# opam.net
KiCad netlist of a schematic drawn in EAGLE
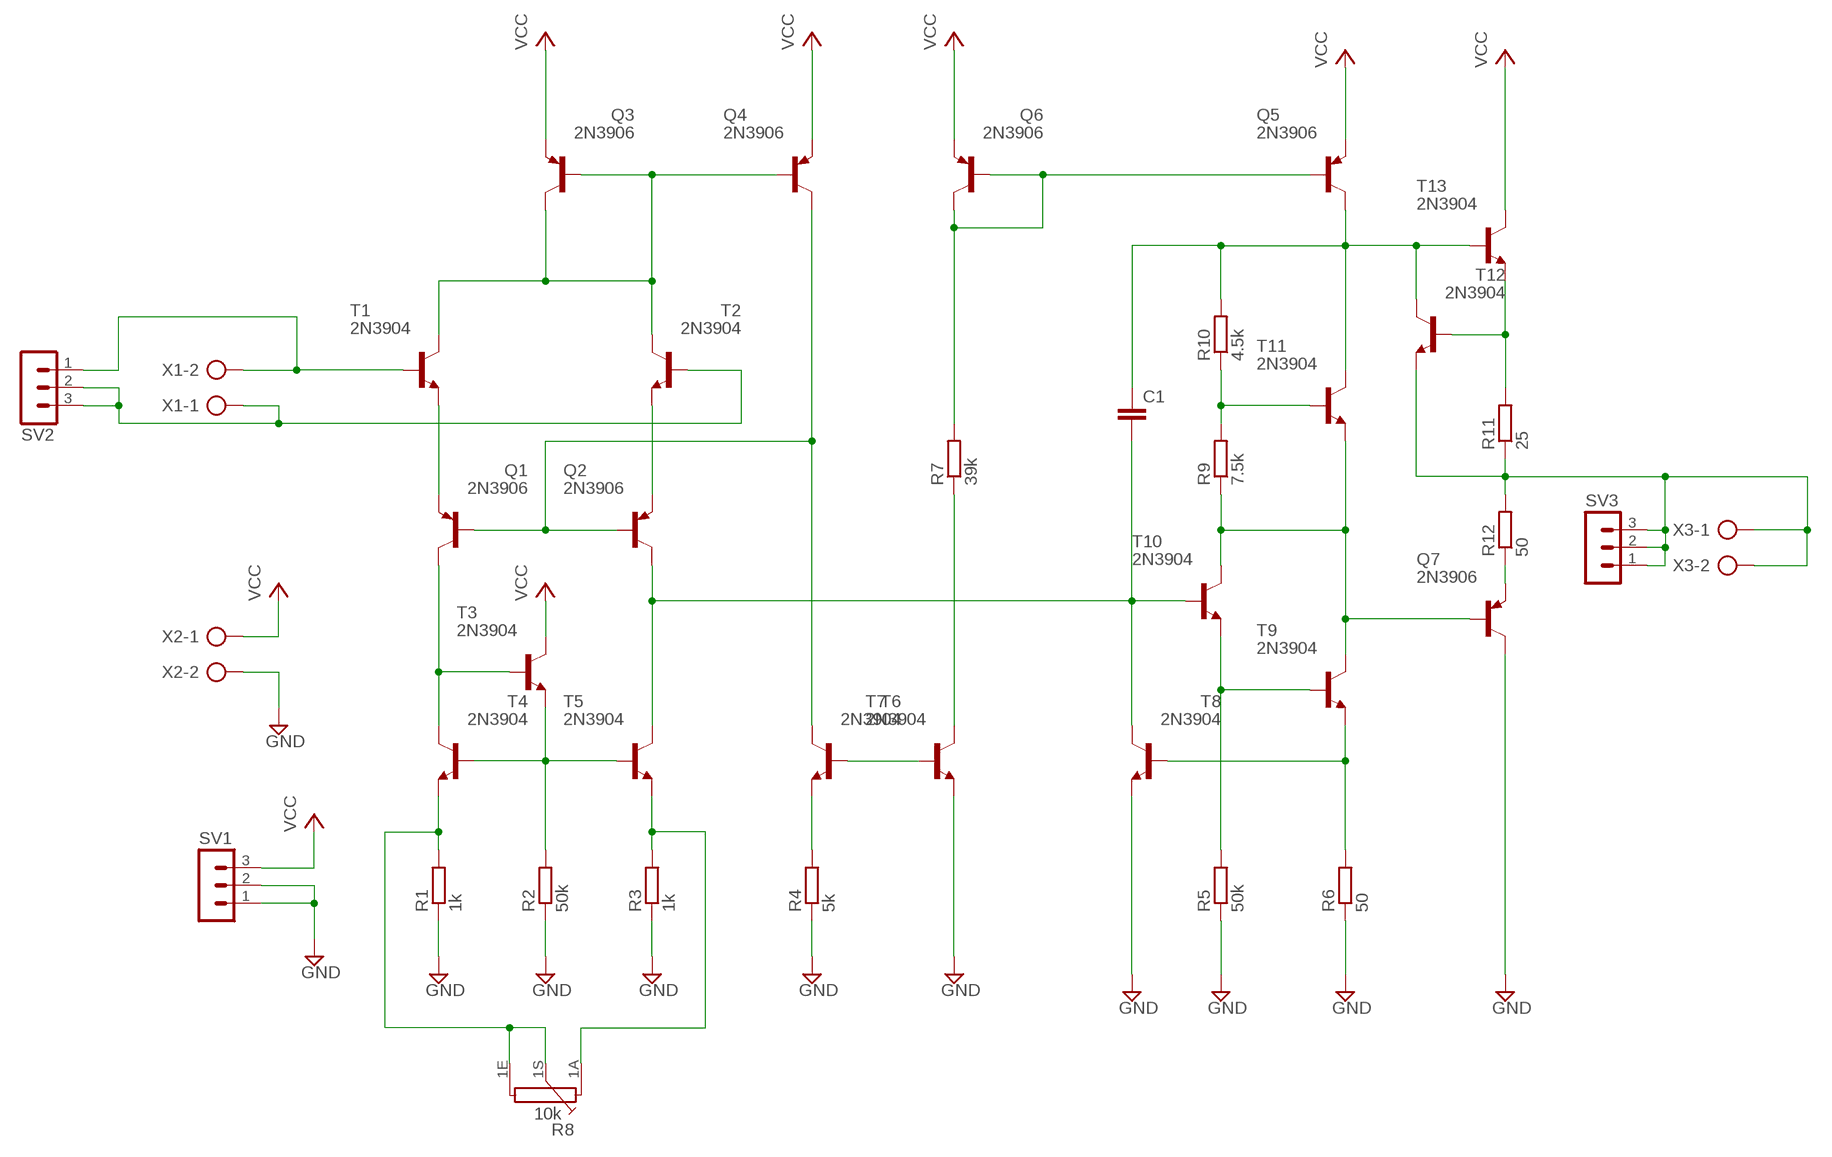
[diagram p0: schematic, sheet 1]

(export (version "E")
  (design (tool "Eeschema 10.0.6"))
  (components
    (comp (ref "C1")
      (value "C2.5/5")
      (footprint "eagle-import:C2.5-5")
      (libsource (lib "eagle-import") (part "C2.5/5"))
    )
    (comp (ref "Q1")
      (value "2N3906")
      (footprint "eagle-import:TO92")
      (libsource (lib "eagle-import") (part "2N3906"))
    )
    (comp (ref "Q2")
      (value "2N3906")
      (footprint "eagle-import:TO92")
      (libsource (lib "eagle-import") (part "2N3906"))
    )
    (comp (ref "Q3")
      (value "2N3906")
      (footprint "eagle-import:TO92")
      (libsource (lib "eagle-import") (part "2N3906"))
    )
    (comp (ref "Q4")
      (value "2N3906")
      (footprint "eagle-import:TO92")
      (libsource (lib "eagle-import") (part "2N3906"))
    )
    (comp (ref "Q5")
      (value "2N3906")
      (footprint "eagle-import:TO92")
      (libsource (lib "eagle-import") (part "2N3906"))
    )
    (comp (ref "Q6")
      (value "2N3906")
      (footprint "eagle-import:TO92")
      (libsource (lib "eagle-import") (part "2N3906"))
    )
    (comp (ref "Q7")
      (value "2N3906")
      (footprint "eagle-import:TO92")
      (libsource (lib "eagle-import") (part "2N3906"))
    )
    (comp (ref "R1")
      (value "1k")
      (footprint "eagle-import:0309_12")
      (libsource (lib "eagle-import") (part "R-EU_0309/12"))
    )
    (comp (ref "R2")
      (value "50k")
      (footprint "eagle-import:0309_12")
      (libsource (lib "eagle-import") (part "R-EU_0309/12"))
    )
    (comp (ref "R3")
      (value "1k")
      (footprint "eagle-import:0309_12")
      (libsource (lib "eagle-import") (part "R-EU_0309/12"))
    )
    (comp (ref "R4")
      (value "5k")
      (footprint "eagle-import:0309_12")
      (libsource (lib "eagle-import") (part "R-EU_0309/12"))
    )
    (comp (ref "R5")
      (value "50k")
      (footprint "eagle-import:0309_12")
      (libsource (lib "eagle-import") (part "R-EU_0309/12"))
    )
    (comp (ref "R6")
      (value "50")
      (footprint "eagle-import:0309_12")
      (libsource (lib "eagle-import") (part "R-EU_0309/12"))
    )
    (comp (ref "R7")
      (value "39k")
      (footprint "eagle-import:0309_12")
      (libsource (lib "eagle-import") (part "R-EU_0309/12"))
    )
    (comp (ref "R8")
      (value "10k")
      (footprint "eagle-import:PC16S")
      (libsource (lib "eagle-import") (part "PC16S"))
    )
    (comp (ref "R9")
      (value "7.5k")
      (footprint "eagle-import:0309_12")
      (libsource (lib "eagle-import") (part "R-EU_0309/12"))
    )
    (comp (ref "R10")
      (value "4.5k")
      (footprint "eagle-import:0309_12")
      (libsource (lib "eagle-import") (part "R-EU_0309/12"))
    )
    (comp (ref "R11")
      (value "25")
      (footprint "eagle-import:0309_12")
      (libsource (lib "eagle-import") (part "R-EU_0309/12"))
    )
    (comp (ref "R12")
      (value "50")
      (footprint "eagle-import:0309_12")
      (libsource (lib "eagle-import") (part "R-EU_0309/12"))
    )
    (comp (ref "SV1")
      (value "MA03-1")
      (footprint "eagle-import:MA03-1")
      (libsource (lib "eagle-import") (part "MA03-1"))
    )
    (comp (ref "SV2")
      (value "MA03-1")
      (footprint "eagle-import:MA03-1")
      (libsource (lib "eagle-import") (part "MA03-1"))
    )
    (comp (ref "SV3")
      (value "MA03-1")
      (footprint "eagle-import:MA03-1")
      (libsource (lib "eagle-import") (part "MA03-1"))
    )
    (comp (ref "T1")
      (value "2N3904")
      (footprint "eagle-import:TO92")
      (libsource (lib "eagle-import") (part "2N3904"))
    )
    (comp (ref "T2")
      (value "2N3904")
      (footprint "eagle-import:TO92")
      (libsource (lib "eagle-import") (part "2N3904"))
    )
    (comp (ref "T3")
      (value "2N3904")
      (footprint "eagle-import:TO92")
      (libsource (lib "eagle-import") (part "2N3904"))
    )
    (comp (ref "T4")
      (value "2N3904")
      (footprint "eagle-import:TO92")
      (libsource (lib "eagle-import") (part "2N3904"))
    )
    (comp (ref "T5")
      (value "2N3904")
      (footprint "eagle-import:TO92")
      (libsource (lib "eagle-import") (part "2N3904"))
    )
    (comp (ref "T6")
      (value "2N3904")
      (footprint "eagle-import:TO92")
      (libsource (lib "eagle-import") (part "2N3904"))
    )
    (comp (ref "T7")
      (value "2N3904")
      (footprint "eagle-import:TO92")
      (libsource (lib "eagle-import") (part "2N3904"))
    )
    (comp (ref "T8")
      (value "2N3904")
      (footprint "eagle-import:TO92")
      (libsource (lib "eagle-import") (part "2N3904"))
    )
    (comp (ref "T9")
      (value "2N3904")
      (footprint "eagle-import:TO92")
      (libsource (lib "eagle-import") (part "2N3904"))
    )
    (comp (ref "T10")
      (value "2N3904")
      (footprint "eagle-import:TO92")
      (libsource (lib "eagle-import") (part "2N3904"))
    )
    (comp (ref "T11")
      (value "2N3904")
      (footprint "eagle-import:TO92")
      (libsource (lib "eagle-import") (part "2N3904"))
    )
    (comp (ref "T12")
      (value "2N3904")
      (footprint "eagle-import:TO92")
      (libsource (lib "eagle-import") (part "2N3904"))
    )
    (comp (ref "T13")
      (value "2N3904")
      (footprint "eagle-import:TO92")
      (libsource (lib "eagle-import") (part "2N3904"))
    )
    (comp (ref "X1")
      (value "AK500/2-H")
      (footprint "eagle-import:AK500_2-H")
      (libsource (lib "eagle-import") (part "AK500/2-H"))
    )
    (comp (ref "X2")
      (value "AK500/2-H")
      (footprint "eagle-import:AK500_2-H")
      (libsource (lib "eagle-import") (part "AK500/2-H"))
    )
    (comp (ref "X3")
      (value "AK500/2-H")
      (footprint "eagle-import:AK500_2-H")
      (libsource (lib "eagle-import") (part "AK500/2-H"))
    )
  )
  (nets
    (net (code "1") (name "GND") (class "Default")
      (node (ref "Q7") (pin "1") (pinfunction "C_1") (pintype "passive"))
      (node (ref "R1") (pin "1") (pinfunction "1_1") (pintype "passive"))
      (node (ref "R2") (pin "1") (pinfunction "1_1") (pintype "passive"))
      (node (ref "R3") (pin "1") (pinfunction "1_1") (pintype "passive"))
      (node (ref "R4") (pin "1") (pinfunction "1_1") (pintype "passive"))
      (node (ref "R5") (pin "1") (pinfunction "1_1") (pintype "passive"))
      (node (ref "R6") (pin "1") (pinfunction "1_1") (pintype "passive"))
      (node (ref "SV1") (pin "1") (pinfunction "1_1") (pintype "passive"))
      (node (ref "SV1") (pin "2") (pinfunction "2_2") (pintype "passive"))
      (node (ref "T7") (pin "3") (pinfunction "E_3") (pintype "passive"))
      (node (ref "T8") (pin "3") (pinfunction "E_3") (pintype "passive"))
      (node (ref "X2") (pin "2") (pinfunction "KL_2") (pintype "passive"))
    )
    (net (code "2") (name "Net-(Q1-B)") (class "Default")
      (node (ref "Q1") (pin "2") (pinfunction "B_2") (pintype "passive"))
      (node (ref "Q2") (pin "2") (pinfunction "B_2") (pintype "passive"))
      (node (ref "Q4") (pin "1") (pinfunction "C_1") (pintype "passive"))
      (node (ref "T6") (pin "1") (pinfunction "C_1") (pintype "passive"))
    )
    (net (code "3") (name "Net-(Q1-C)") (class "Default")
      (node (ref "Q1") (pin "1") (pinfunction "C_1") (pintype "passive"))
      (node (ref "T3") (pin "2") (pinfunction "B_2") (pintype "passive"))
      (node (ref "T4") (pin "1") (pinfunction "C_1") (pintype "passive"))
    )
    (net (code "4") (name "Net-(Q1-E)") (class "Default")
      (node (ref "Q1") (pin "3") (pinfunction "E_3") (pintype "passive"))
      (node (ref "T1") (pin "3") (pinfunction "E_3") (pintype "passive"))
    )
    (net (code "5") (name "Net-(Q2-C)") (class "Default")
      (node (ref "C1") (pin "2") (pinfunction "2_2") (pintype "passive"))
      (node (ref "Q2") (pin "1") (pinfunction "C_1") (pintype "passive"))
      (node (ref "T10") (pin "2") (pinfunction "B_2") (pintype "passive"))
      (node (ref "T5") (pin "1") (pinfunction "C_1") (pintype "passive"))
      (node (ref "T8") (pin "1") (pinfunction "C_1") (pintype "passive"))
    )
    (net (code "6") (name "Net-(Q2-E)") (class "Default")
      (node (ref "Q2") (pin "3") (pinfunction "E_3") (pintype "passive"))
      (node (ref "T2") (pin "3") (pinfunction "E_3") (pintype "passive"))
    )
    (net (code "7") (name "Net-(Q3-B)") (class "Default")
      (node (ref "Q3") (pin "1") (pinfunction "C_1") (pintype "passive"))
      (node (ref "Q3") (pin "2") (pinfunction "B_2") (pintype "passive"))
      (node (ref "Q4") (pin "2") (pinfunction "B_2") (pintype "passive"))
      (node (ref "T1") (pin "1") (pinfunction "C_1") (pintype "passive"))
      (node (ref "T2") (pin "1") (pinfunction "C_1") (pintype "passive"))
    )
    (net (code "8") (name "Net-(Q5-B)") (class "Default")
      (node (ref "Q5") (pin "2") (pinfunction "B_2") (pintype "passive"))
      (node (ref "Q6") (pin "1") (pinfunction "C_1") (pintype "passive"))
      (node (ref "Q6") (pin "2") (pinfunction "B_2") (pintype "passive"))
      (node (ref "R7") (pin "2") (pinfunction "2_2") (pintype "passive"))
    )
    (net (code "9") (name "Net-(Q5-C)") (class "Default")
      (node (ref "C1") (pin "1") (pinfunction "1_1") (pintype "passive"))
      (node (ref "Q5") (pin "1") (pinfunction "C_1") (pintype "passive"))
      (node (ref "R10") (pin "2") (pinfunction "2_2") (pintype "passive"))
      (node (ref "T11") (pin "1") (pinfunction "C_1") (pintype "passive"))
      (node (ref "T12") (pin "1") (pinfunction "C_1") (pintype "passive"))
      (node (ref "T13") (pin "2") (pinfunction "B_2") (pintype "passive"))
    )
    (net (code "10") (name "Net-(Q7-B)") (class "Default")
      (node (ref "Q7") (pin "2") (pinfunction "B_2") (pintype "passive"))
      (node (ref "R9") (pin "1") (pinfunction "1_1") (pintype "passive"))
      (node (ref "T10") (pin "1") (pinfunction "C_1") (pintype "passive"))
      (node (ref "T11") (pin "3") (pinfunction "E_3") (pintype "passive"))
      (node (ref "T9") (pin "1") (pinfunction "C_1") (pintype "passive"))
    )
    (net (code "11") (name "Net-(Q7-E)") (class "Default")
      (node (ref "Q7") (pin "3") (pinfunction "E_3") (pintype "passive"))
      (node (ref "R12") (pin "1") (pinfunction "1_1") (pintype "passive"))
    )
    (net (code "12") (name "Net-(T1-B)") (class "Default")
      (node (ref "SV2") (pin "1") (pinfunction "1_1") (pintype "passive"))
      (node (ref "T1") (pin "2") (pinfunction "B_2") (pintype "passive"))
      (node (ref "X1") (pin "2") (pinfunction "KL_2") (pintype "passive"))
    )
    (net (code "13") (name "Net-(T2-B)") (class "Default")
      (node (ref "SV2") (pin "2") (pinfunction "2_2") (pintype "passive"))
      (node (ref "SV2") (pin "3") (pinfunction "3_3") (pintype "passive"))
      (node (ref "T2") (pin "2") (pinfunction "B_2") (pintype "passive"))
      (node (ref "X1") (pin "1") (pinfunction "KL_1") (pintype "passive"))
    )
    (net (code "14") (name "Net-(T3-E)") (class "Default")
      (node (ref "R2") (pin "2") (pinfunction "2_2") (pintype "passive"))
      (node (ref "T3") (pin "3") (pinfunction "E_3") (pintype "passive"))
      (node (ref "T4") (pin "2") (pinfunction "B_2") (pintype "passive"))
      (node (ref "T5") (pin "2") (pinfunction "B_2") (pintype "passive"))
    )
    (net (code "15") (name "Net-(T4-E)") (class "Default")
      (node (ref "R1") (pin "2") (pinfunction "2_2") (pintype "passive"))
      (node (ref "R8") (pin "1E") (pinfunction "1E_1E") (pintype "passive"))
      (node (ref "R8") (pin "1S") (pinfunction "1S_1S") (pintype "passive"))
      (node (ref "T4") (pin "3") (pinfunction "E_3") (pintype "passive"))
    )
    (net (code "16") (name "Net-(T5-E)") (class "Default")
      (node (ref "R3") (pin "2") (pinfunction "2_2") (pintype "passive"))
      (node (ref "R8") (pin "1A") (pinfunction "1A_1A") (pintype "passive"))
      (node (ref "T5") (pin "3") (pinfunction "E_3") (pintype "passive"))
    )
    (net (code "17") (name "Net-(T6-B)") (class "Default")
      (node (ref "T6") (pin "2") (pinfunction "B_2") (pintype "passive"))
      (node (ref "T7") (pin "2") (pinfunction "B_2") (pintype "passive"))
    )
    (net (code "18") (name "Net-(T6-E)") (class "Default")
      (node (ref "R4") (pin "2") (pinfunction "2_2") (pintype "passive"))
      (node (ref "T6") (pin "3") (pinfunction "E_3") (pintype "passive"))
    )
    (net (code "19") (name "Net-(T7-C)") (class "Default")
      (node (ref "R7") (pin "1") (pinfunction "1_1") (pintype "passive"))
      (node (ref "T7") (pin "1") (pinfunction "C_1") (pintype "passive"))
    )
    (net (code "20") (name "Net-(T8-B)") (class "Default")
      (node (ref "R6") (pin "2") (pinfunction "2_2") (pintype "passive"))
      (node (ref "T8") (pin "2") (pinfunction "B_2") (pintype "passive"))
      (node (ref "T9") (pin "3") (pinfunction "E_3") (pintype "passive"))
    )
    (net (code "21") (name "Net-(T10-E)") (class "Default")
      (node (ref "R5") (pin "2") (pinfunction "2_2") (pintype "passive"))
      (node (ref "T10") (pin "3") (pinfunction "E_3") (pintype "passive"))
      (node (ref "T9") (pin "2") (pinfunction "B_2") (pintype "passive"))
    )
    (net (code "22") (name "Net-(T11-B)") (class "Default")
      (node (ref "R10") (pin "1") (pinfunction "1_1") (pintype "passive"))
      (node (ref "R9") (pin "2") (pinfunction "2_2") (pintype "passive"))
      (node (ref "T11") (pin "2") (pinfunction "B_2") (pintype "passive"))
    )
    (net (code "23") (name "Net-(T12-B)") (class "Default")
      (node (ref "R11") (pin "2") (pinfunction "2_2") (pintype "passive"))
      (node (ref "T12") (pin "2") (pinfunction "B_2") (pintype "passive"))
      (node (ref "T13") (pin "3") (pinfunction "E_3") (pintype "passive"))
    )
    (net (code "24") (name "Net-(T12-E)") (class "Default")
      (node (ref "R11") (pin "1") (pinfunction "1_1") (pintype "passive"))
      (node (ref "R12") (pin "2") (pinfunction "2_2") (pintype "passive"))
      (node (ref "SV3") (pin "1") (pinfunction "1_1") (pintype "passive"))
      (node (ref "SV3") (pin "2") (pinfunction "2_2") (pintype "passive"))
      (node (ref "SV3") (pin "3") (pinfunction "3_3") (pintype "passive"))
      (node (ref "T12") (pin "3") (pinfunction "E_3") (pintype "passive"))
      (node (ref "X3") (pin "1") (pinfunction "KL_1") (pintype "passive"))
      (node (ref "X3") (pin "2") (pinfunction "KL_2") (pintype "passive"))
    )
    (net (code "25") (name "VCC") (class "Default")
      (node (ref "Q3") (pin "3") (pinfunction "E_3") (pintype "passive"))
      (node (ref "Q4") (pin "3") (pinfunction "E_3") (pintype "passive"))
      (node (ref "Q5") (pin "3") (pinfunction "E_3") (pintype "passive"))
      (node (ref "Q6") (pin "3") (pinfunction "E_3") (pintype "passive"))
      (node (ref "SV1") (pin "3") (pinfunction "3_3") (pintype "passive"))
      (node (ref "T13") (pin "1") (pinfunction "C_1") (pintype "passive"))
      (node (ref "T3") (pin "1") (pinfunction "C_1") (pintype "passive"))
      (node (ref "X2") (pin "1") (pinfunction "KL_1") (pintype "passive"))
    )
  )
)
